# SuperPower.net
KiCad netlist of a schematic drawn in Altium Designer
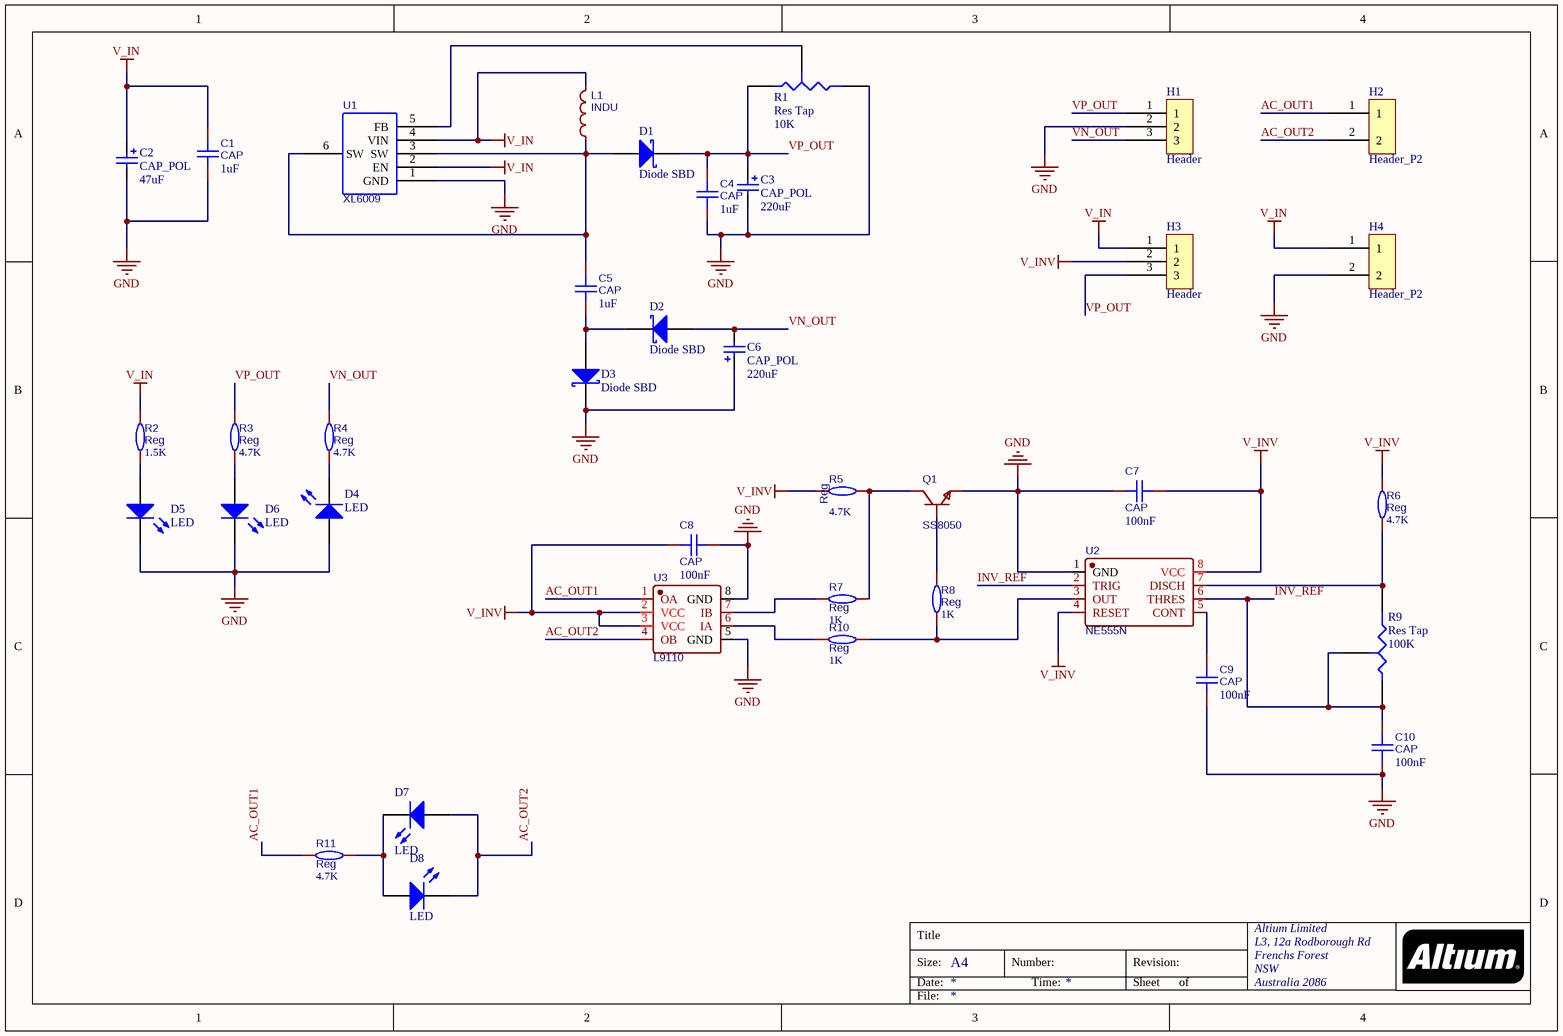
[diagram p0: SuperPower.SchDoc]

(export (version "E")
  (design (tool "Eeschema 10.0.6"))
  (components
    (comp (ref "C1")
      (value "CAP")
      (footprint "C0603")
      (description "Cap")
      (fields
        (field (name "BOM_SUPPLIER PART") "C302008")
        (field (name "BOM_MANUFACTURER PART") "0603B103K101CT")
        (field (name "ALTIUM_VALUE") "1uF")
        (field (name "CONTRIBUTOR") "LCSC")
      )
      (libsource (lib "Levent_lib") (part "CAP"))
    )
    (comp (ref "C2")
      (value "CAP_POL")
      (footprint "CAP_SMD_10mm")
      (description "极性电容")
      (fields (field (name "ALTIUM_VALUE") "47uF"))
      (libsource (lib "Levent_lib") (part "CAP_POL"))
    )
    (comp (ref "C3")
      (value "CAP_POL")
      (footprint "CAP_SMD_10mm")
      (description "极性电容")
      (fields (field (name "ALTIUM_VALUE") "220uF"))
      (libsource (lib "Levent_lib") (part "CAP_POL"))
    )
    (comp (ref "C4")
      (value "CAP")
      (footprint "C0603")
      (description "Cap")
      (fields
        (field (name "BOM_SUPPLIER PART") "C302008")
        (field (name "BOM_MANUFACTURER PART") "0603B103K101CT")
        (field (name "ALTIUM_VALUE") "1uF")
        (field (name "CONTRIBUTOR") "LCSC")
      )
      (libsource (lib "Levent_lib") (part "CAP"))
    )
    (comp (ref "C5")
      (value "CAP")
      (footprint "C0603")
      (description "Cap")
      (fields
        (field (name "BOM_SUPPLIER PART") "C302008")
        (field (name "BOM_MANUFACTURER PART") "0603B103K101CT")
        (field (name "ALTIUM_VALUE") "1uF")
        (field (name "CONTRIBUTOR") "LCSC")
      )
      (libsource (lib "Levent_lib") (part "CAP"))
    )
    (comp (ref "C6")
      (value "CAP_POL")
      (footprint "CAP_SMD_10mm")
      (description "极性电容")
      (fields (field (name "ALTIUM_VALUE") "220uF"))
      (libsource (lib "Levent_lib") (part "CAP_POL"))
    )
    (comp (ref "C7")
      (value "CAP")
      (footprint "C0603")
      (description "Cap")
      (fields
        (field (name "BOM_SUPPLIER PART") "C302008")
        (field (name "BOM_MANUFACTURER PART") "0603B103K101CT")
        (field (name "ALTIUM_VALUE") "100nF")
        (field (name "CONTRIBUTOR") "LCSC")
      )
      (libsource (lib "Levent_lib") (part "CAP"))
    )
    (comp (ref "C8")
      (value "CAP")
      (footprint "C0603")
      (description "Cap")
      (fields
        (field (name "BOM_SUPPLIER PART") "C302008")
        (field (name "BOM_MANUFACTURER PART") "0603B103K101CT")
        (field (name "ALTIUM_VALUE") "100nF")
        (field (name "CONTRIBUTOR") "LCSC")
      )
      (libsource (lib "Levent_lib") (part "CAP"))
    )
    (comp (ref "C9")
      (value "CAP")
      (footprint "C0603")
      (description "Cap")
      (fields
        (field (name "BOM_SUPPLIER PART") "C302008")
        (field (name "BOM_MANUFACTURER PART") "0603B103K101CT")
        (field (name "ALTIUM_VALUE") "100nF")
        (field (name "CONTRIBUTOR") "LCSC")
      )
      (libsource (lib "Levent_lib") (part "CAP"))
    )
    (comp (ref "C10")
      (value "CAP")
      (footprint "C0603")
      (description "Cap")
      (fields
        (field (name "BOM_SUPPLIER PART") "C302008")
        (field (name "BOM_MANUFACTURER PART") "0603B103K101CT")
        (field (name "ALTIUM_VALUE") "100nF")
        (field (name "CONTRIBUTOR") "LCSC")
      )
      (libsource (lib "Levent_lib") (part "CAP"))
    )
    (comp (ref "D1")
      (value "Diode SBD")
      (footprint "SMA_L4.3")
      (description "Schottky Rectifier")
      (fields (field (name "PUBLISHER") "Altium Limited"))
      (libsource (lib "Levent_lib") (part "Diode SBD"))
    )
    (comp (ref "D2")
      (value "Diode SBD")
      (footprint "SMA_L4.3")
      (description "Schottky Rectifier")
      (fields (field (name "PUBLISHER") "Altium Limited"))
      (libsource (lib "Levent_lib") (part "Diode SBD"))
    )
    (comp (ref "D3")
      (value "Diode SBD")
      (footprint "SMA_L4.3")
      (description "Schottky Rectifier")
      (fields (field (name "PUBLISHER") "Altium Limited"))
      (libsource (lib "Levent_lib") (part "Diode SBD"))
    )
    (comp (ref "D4")
      (value "LED")
      (footprint "LED0603")
      (fields (field (name "PUBLISHER") "Altium Limited"))
      (libsource (lib "Levent_lib") (part "LED0"))
    )
    (comp (ref "D5")
      (value "LED")
      (footprint "LED0603")
      (fields (field (name "PUBLISHER") "Altium Limited"))
      (libsource (lib "Levent_lib") (part "LED0"))
    )
    (comp (ref "D6")
      (value "LED")
      (footprint "LED0603")
      (fields (field (name "PUBLISHER") "Altium Limited"))
      (libsource (lib "Levent_lib") (part "LED0"))
    )
    (comp (ref "D7")
      (value "LED")
      (footprint "LED0603")
      (fields (field (name "PUBLISHER") "Altium Limited"))
      (libsource (lib "Levent_lib") (part "LED0"))
    )
    (comp (ref "D8")
      (value "LED")
      (footprint "LED0603")
      (fields (field (name "PUBLISHER") "Altium Limited"))
      (libsource (lib "Levent_lib") (part "LED0"))
    )
    (comp (ref "H1")
      (value "Header")
      (footprint "H_2.54_P3")
      (description "3Pin接口")
      (libsource (lib "Levent_lib") (part "Header_P3"))
    )
    (comp (ref "H2")
      (value "Header_P2")
      (footprint "H_2.54_P2")
      (description "2Pin排针")
      (libsource (lib "Levent_lib") (part "Header_P2"))
    )
    (comp (ref "H3")
      (value "Header")
      (footprint "H_2.54_P3")
      (description "3Pin接口")
      (libsource (lib "Levent_lib") (part "Header_P3"))
    )
    (comp (ref "H4")
      (value "Header_P2")
      (footprint "H_2.54_P2")
      (description "2Pin排针")
      (libsource (lib "Levent_lib") (part "Header_P2"))
    )
    (comp (ref "L1")
      (value "INDU")
      (footprint "SMD_L7.1")
      (description "电感")
      (fields
        (field (name "BOM_SUPPLIER PART") "C182182")
        (field (name "BOM_MANUFACTURER PART") "SLO0630H150MTT")
        (field (name "CONTRIBUTOR") "LCSC")
      )
      (libsource (lib "Levent_lib") (part "IND"))
    )
    (comp (ref "Q1")
      (value "SS8050")
      (footprint "SOT-23-3")
      (description "NPN")
      (fields (field (name "BOM_SUPPLIER PART") "C541705") (field (name "CONTRIBUTOR") "LCSC"))
      (libsource (lib "Levent_lib") (part "SS8050"))
    )
    (comp (ref "R1")
      (value "Res Tap")
      (footprint "Res_Tap_3296")
      (description "可调电阻")
      (fields (field (name "ALTIUM_VALUE") "10K") (field (name "PUBLISHER") "Altium Limited"))
      (libsource (lib "Levent_lib") (part "Res Tap"))
    )
    (comp (ref "R2")
      (value "Reg")
      (footprint "R0603")
      (description "电阻")
      (fields
        (field (name "BOM_SUPPLIER PART") "C465721")
        (field (name "BOM_MANUFACTURER PART") "AR03BTCX1002A")
        (field (name "ALTIUM_VALUE") "1.5K")
        (field (name "CONTRIBUTOR") "LCSC")
      )
      (libsource (lib "Levent_lib") (part "Res"))
    )
    (comp (ref "R3")
      (value "Reg")
      (footprint "R0603")
      (description "电阻")
      (fields
        (field (name "BOM_SUPPLIER PART") "C465721")
        (field (name "BOM_MANUFACTURER PART") "AR03BTCX1002A")
        (field (name "ALTIUM_VALUE") "4.7K")
        (field (name "CONTRIBUTOR") "LCSC")
      )
      (libsource (lib "Levent_lib") (part "Res"))
    )
    (comp (ref "R4")
      (value "Reg")
      (footprint "R0603")
      (description "电阻")
      (fields
        (field (name "BOM_SUPPLIER PART") "C465721")
        (field (name "BOM_MANUFACTURER PART") "AR03BTCX1002A")
        (field (name "ALTIUM_VALUE") "4.7K")
        (field (name "CONTRIBUTOR") "LCSC")
      )
      (libsource (lib "Levent_lib") (part "Res"))
    )
    (comp (ref "R5")
      (value "Reg")
      (footprint "R0603")
      (description "电阻")
      (fields
        (field (name "BOM_SUPPLIER PART") "C465721")
        (field (name "BOM_MANUFACTURER PART") "AR03BTCX1002A")
        (field (name "ALTIUM_VALUE") "4.7K")
        (field (name "CONTRIBUTOR") "LCSC")
      )
      (libsource (lib "Levent_lib") (part "Res"))
    )
    (comp (ref "R6")
      (value "Reg")
      (footprint "R0603")
      (description "电阻")
      (fields
        (field (name "BOM_SUPPLIER PART") "C465721")
        (field (name "BOM_MANUFACTURER PART") "AR03BTCX1002A")
        (field (name "ALTIUM_VALUE") "4.7K")
        (field (name "CONTRIBUTOR") "LCSC")
      )
      (libsource (lib "Levent_lib") (part "Res"))
    )
    (comp (ref "R7")
      (value "Reg")
      (footprint "R0603")
      (description "电阻")
      (fields
        (field (name "BOM_SUPPLIER PART") "C465721")
        (field (name "BOM_MANUFACTURER PART") "AR03BTCX1002A")
        (field (name "ALTIUM_VALUE") "1K")
        (field (name "CONTRIBUTOR") "LCSC")
      )
      (libsource (lib "Levent_lib") (part "Res"))
    )
    (comp (ref "R8")
      (value "Reg")
      (footprint "R0603")
      (description "电阻")
      (fields
        (field (name "BOM_SUPPLIER PART") "C465721")
        (field (name "BOM_MANUFACTURER PART") "AR03BTCX1002A")
        (field (name "ALTIUM_VALUE") "1K")
        (field (name "CONTRIBUTOR") "LCSC")
      )
      (libsource (lib "Levent_lib") (part "Res"))
    )
    (comp (ref "R9")
      (value "Res Tap")
      (footprint "Res_Tap_3296")
      (description "可调电阻")
      (fields (field (name "ALTIUM_VALUE") "100K") (field (name "PUBLISHER") "Altium Limited"))
      (libsource (lib "Levent_lib") (part "Res Tap"))
    )
    (comp (ref "R10")
      (value "Reg")
      (footprint "R0603")
      (description "电阻")
      (fields
        (field (name "BOM_SUPPLIER PART") "C465721")
        (field (name "BOM_MANUFACTURER PART") "AR03BTCX1002A")
        (field (name "ALTIUM_VALUE") "1K")
        (field (name "CONTRIBUTOR") "LCSC")
      )
      (libsource (lib "Levent_lib") (part "Res"))
    )
    (comp (ref "R11")
      (value "Reg")
      (footprint "R0603")
      (description "电阻")
      (fields
        (field (name "BOM_SUPPLIER PART") "C465721")
        (field (name "BOM_MANUFACTURER PART") "AR03BTCX1002A")
        (field (name "ALTIUM_VALUE") "4.7K")
        (field (name "CONTRIBUTOR") "LCSC")
      )
      (libsource (lib "Levent_lib") (part "Res"))
    )
    (comp (ref "U1")
      (value "XL6009")
      (footprint "TO-263-5")
      (fields
        (field (name "BOM_MANUFACTURER PART") "LM2577SX-ADJ/NOPB")
        (field (name "BOM_SUPPLIER PART") "C17117")
      )
      (libsource (lib "Levent_lib") (part "XL6009"))
    )
    (comp (ref "U2")
      (value "NE555N")
      (footprint "DIP-8")
      (description "NE555_IC")
      (fields (field (name "BOM_SUPPLIER PART") "C398063") (field (name "CONTRIBUTOR") "LCSC"))
      (libsource (lib "Levent_lib") (part "NE555N"))
    )
    (comp (ref "U3")
      (value "L9110")
      (footprint "DIP-8")
      (description "L9110_HBridge")
      (fields
        (field (name "BOM_SUPPLIER PART") "C513306")
        (field (name "BOM_MANUFACTURER PART") "L9110S")
        (field (name "CONTRIBUTOR") "LCSC")
      )
      (libsource (lib "Levent_lib") (part "L9110"))
    )
  )
  (nets
    (net (code "1") (name "/AC_OUT1") (class "Default")
      (node (ref "H2") (pin "1") (pinfunction "1_1") (pintype "passive"))
      (node (ref "R11") (pin "1") (pinfunction "1_1") (pintype "passive"))
      (node (ref "U3") (pin "1") (pinfunction "OA_1") (pintype "passive"))
    )
    (net (code "2") (name "/AC_OUT2") (class "Default")
      (node (ref "D7") (pin "2") (pinfunction "A_2") (pintype "passive"))
      (node (ref "D8") (pin "1") (pinfunction "K_1") (pintype "passive"))
      (node (ref "H2") (pin "2") (pinfunction "2_2") (pintype "passive"))
      (node (ref "U3") (pin "4") (pinfunction "OB_4") (pintype "passive"))
    )
    (net (code "3") (name "/INV_REF") (class "Default")
      (node (ref "C10") (pin "1") (pinfunction "1_1") (pintype "passive"))
      (node (ref "R9") (pin "1") (pinfunction "A_1") (pintype "passive"))
      (node (ref "R9") (pin "3") (pinfunction "TAP_3") (pintype "passive"))
      (node (ref "U2") (pin "2") (pinfunction "TRIG_2") (pintype "passive"))
      (node (ref "U2") (pin "6") (pinfunction "THRES_6") (pintype "passive"))
    )
    (net (code "4") (name "/VN_OUT") (class "Default")
      (node (ref "C6") (pin "2") (pinfunction "2_2") (pintype "passive"))
      (node (ref "D2") (pin "2") (pinfunction "A_2") (pintype "passive"))
      (node (ref "H1") (pin "3") (pinfunction "3_3") (pintype "passive"))
      (node (ref "R4") (pin "1") (pinfunction "1_1") (pintype "passive"))
    )
    (net (code "5") (name "/VP_OUT") (class "Default")
      (node (ref "C3") (pin "1") (pinfunction "1_1") (pintype "passive"))
      (node (ref "C4") (pin "1") (pinfunction "1_1") (pintype "passive"))
      (node (ref "D1") (pin "1") (pinfunction "K_1") (pintype "passive"))
      (node (ref "H1") (pin "1") (pinfunction "1_1") (pintype "passive"))
      (node (ref "H3") (pin "3") (pinfunction "3_3") (pintype "passive"))
      (node (ref "R1") (pin "1") (pinfunction "A_1") (pintype "passive"))
      (node (ref "R3") (pin "1") (pinfunction "1_1") (pintype "passive"))
    )
    (net (code "6") (name "GND") (class "Default")
      (node (ref "C1") (pin "2") (pinfunction "2_2") (pintype "passive"))
      (node (ref "C10") (pin "2") (pinfunction "2_2") (pintype "passive"))
      (node (ref "C2") (pin "2") (pinfunction "2_2") (pintype "passive"))
      (node (ref "C3") (pin "2") (pinfunction "2_2") (pintype "passive"))
      (node (ref "C4") (pin "2") (pinfunction "2_2") (pintype "passive"))
      (node (ref "C6") (pin "1") (pinfunction "1_1") (pintype "passive"))
      (node (ref "C7") (pin "1") (pinfunction "1_1") (pintype "passive"))
      (node (ref "C8") (pin "2") (pinfunction "2_2") (pintype "passive"))
      (node (ref "C9") (pin "2") (pinfunction "2_2") (pintype "passive"))
      (node (ref "D3") (pin "1") (pinfunction "K_1") (pintype "passive"))
      (node (ref "D4") (pin "2") (pinfunction "A_2") (pintype "passive"))
      (node (ref "D5") (pin "1") (pinfunction "K_1") (pintype "passive"))
      (node (ref "D6") (pin "1") (pinfunction "K_1") (pintype "passive"))
      (node (ref "H1") (pin "2") (pinfunction "2_2") (pintype "passive"))
      (node (ref "H4") (pin "2") (pinfunction "2_2") (pintype "passive"))
      (node (ref "Q1") (pin "2") (pinfunction "E_2") (pintype "passive"))
      (node (ref "R1") (pin "2") (pinfunction "B_2") (pintype "passive"))
      (node (ref "U1") (pin "1") (pinfunction "GND_1") (pintype "passive"))
      (node (ref "U2") (pin "1") (pinfunction "GND_1") (pintype "passive"))
      (node (ref "U3") (pin "5") (pinfunction "GND_5") (pintype "passive"))
      (node (ref "U3") (pin "8") (pinfunction "GND_8") (pintype "passive"))
    )
    (net (code "7") (name "Net-(D1-A)") (class "Default")
      (node (ref "C5") (pin "1") (pinfunction "1_1") (pintype "passive"))
      (node (ref "D1") (pin "2") (pinfunction "A_2") (pintype "passive"))
      (node (ref "L1") (pin "1") (pinfunction "1_1") (pintype "passive"))
      (node (ref "U1") (pin "3") (pinfunction "SW_3") (pintype "passive"))
      (node (ref "U1") (pin "6") (pinfunction "SW_6") (pintype "passive"))
    )
    (net (code "8") (name "Net-(D2-K)") (class "Default")
      (node (ref "C5") (pin "2") (pinfunction "2_2") (pintype "passive"))
      (node (ref "D2") (pin "1") (pinfunction "K_1") (pintype "passive"))
      (node (ref "D3") (pin "2") (pinfunction "A_2") (pintype "passive"))
    )
    (net (code "9") (name "Net-(D4-K)") (class "Default")
      (node (ref "D4") (pin "1") (pinfunction "K_1") (pintype "passive"))
      (node (ref "R4") (pin "2") (pinfunction "2_2") (pintype "passive"))
    )
    (net (code "10") (name "Net-(D5-A)") (class "Default")
      (node (ref "D5") (pin "2") (pinfunction "A_2") (pintype "passive"))
      (node (ref "R2") (pin "2") (pinfunction "2_2") (pintype "passive"))
    )
    (net (code "11") (name "Net-(D6-A)") (class "Default")
      (node (ref "D6") (pin "2") (pinfunction "A_2") (pintype "passive"))
      (node (ref "R3") (pin "2") (pinfunction "2_2") (pintype "passive"))
    )
    (net (code "12") (name "Net-(D7-K)") (class "Default")
      (node (ref "D7") (pin "1") (pinfunction "K_1") (pintype "passive"))
      (node (ref "D8") (pin "2") (pinfunction "A_2") (pintype "passive"))
      (node (ref "R11") (pin "2") (pinfunction "2_2") (pintype "passive"))
    )
    (net (code "13") (name "Net-(Q1-B)") (class "Default")
      (node (ref "Q1") (pin "1") (pinfunction "B_1") (pintype "passive"))
      (node (ref "R8") (pin "2") (pinfunction "2_2") (pintype "passive"))
    )
    (net (code "14") (name "Net-(Q1-C)") (class "Default")
      (node (ref "Q1") (pin "3") (pinfunction "C_3") (pintype "passive"))
      (node (ref "R5") (pin "1") (pinfunction "1_1") (pintype "passive"))
      (node (ref "R7") (pin "2") (pinfunction "2_2") (pintype "passive"))
    )
    (net (code "15") (name "Net-(R1-TAP)") (class "Default")
      (node (ref "R1") (pin "3") (pinfunction "TAP_3") (pintype "passive"))
      (node (ref "U1") (pin "5") (pinfunction "FB_5") (pintype "passive"))
    )
    (net (code "16") (name "Net-(R9-B)") (class "Default")
      (node (ref "R6") (pin "1") (pinfunction "1_1") (pintype "passive"))
      (node (ref "R9") (pin "2") (pinfunction "B_2") (pintype "passive"))
      (node (ref "U2") (pin "7") (pinfunction "DISCH_7") (pintype "passive"))
    )
    (net (code "17") (name "Net-(U2-CONT)") (class "Default")
      (node (ref "C9") (pin "1") (pinfunction "1_1") (pintype "passive"))
      (node (ref "U2") (pin "5") (pinfunction "CONT_5") (pintype "passive"))
    )
    (net (code "18") (name "Net-(U2-OUT)") (class "Default")
      (node (ref "R10") (pin "2") (pinfunction "2_2") (pintype "passive"))
      (node (ref "R8") (pin "1") (pinfunction "1_1") (pintype "passive"))
      (node (ref "U2") (pin "3") (pinfunction "OUT_3") (pintype "passive"))
    )
    (net (code "19") (name "Net-(U3-IA)") (class "Default")
      (node (ref "R10") (pin "1") (pinfunction "1_1") (pintype "passive"))
      (node (ref "U3") (pin "6") (pinfunction "IA_6") (pintype "passive"))
    )
    (net (code "20") (name "Net-(U3-IB)") (class "Default")
      (node (ref "R7") (pin "1") (pinfunction "1_1") (pintype "passive"))
      (node (ref "U3") (pin "7") (pinfunction "IB_7") (pintype "passive"))
    )
    (net (code "21") (name "V_IN") (class "Default")
      (node (ref "C1") (pin "1") (pinfunction "1_1") (pintype "passive"))
      (node (ref "C2") (pin "1") (pinfunction "1_1") (pintype "passive"))
      (node (ref "H3") (pin "1") (pinfunction "1_1") (pintype "passive"))
      (node (ref "H4") (pin "1") (pinfunction "1_1") (pintype "passive"))
      (node (ref "L1") (pin "2") (pinfunction "2_2") (pintype "passive"))
      (node (ref "R2") (pin "1") (pinfunction "1_1") (pintype "passive"))
      (node (ref "U1") (pin "2") (pinfunction "EN_2") (pintype "passive"))
      (node (ref "U1") (pin "4") (pinfunction "VIN_4") (pintype "passive"))
    )
    (net (code "22") (name "V_INV") (class "Default")
      (node (ref "C7") (pin "2") (pinfunction "2_2") (pintype "passive"))
      (node (ref "C8") (pin "1") (pinfunction "1_1") (pintype "passive"))
      (node (ref "H3") (pin "2") (pinfunction "2_2") (pintype "passive"))
      (node (ref "R5") (pin "2") (pinfunction "2_2") (pintype "passive"))
      (node (ref "R6") (pin "2") (pinfunction "2_2") (pintype "passive"))
      (node (ref "U2") (pin "4") (pinfunction "RESET_4") (pintype "passive"))
      (node (ref "U2") (pin "8") (pinfunction "VCC_8") (pintype "passive"))
      (node (ref "U3") (pin "2") (pinfunction "VCC_2") (pintype "passive"))
      (node (ref "U3") (pin "3") (pinfunction "VCC_3") (pintype "passive"))
    )
  )
)
